# melody.net
KiCad netlist of a schematic drawn in EAGLE
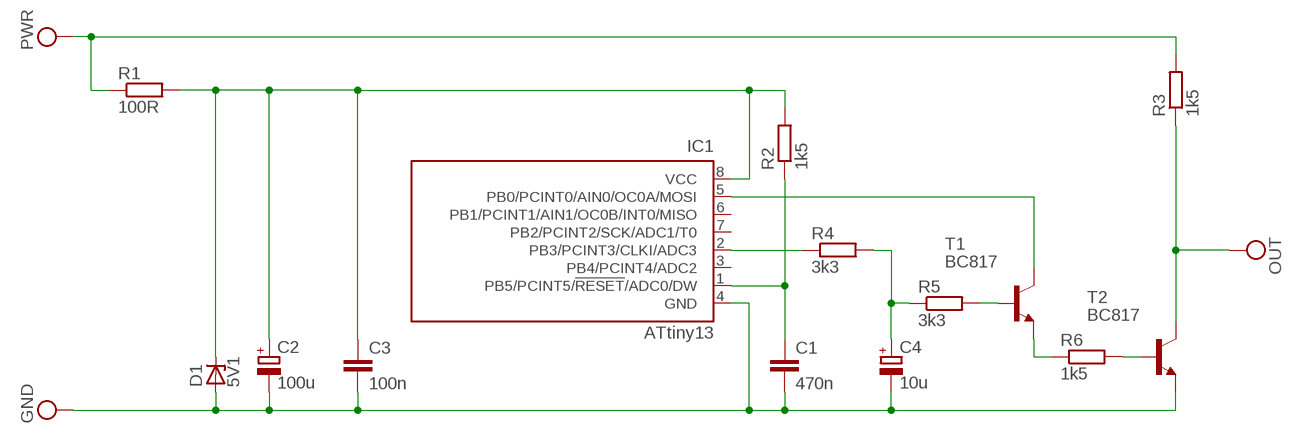
[diagram p0: schematic, sheet 1]

(export (version "E")
  (design (tool "Eeschema 10.0.6"))
  (components
    (comp (ref "C1")
      (value "470n")
      (footprint "eagle-import:C2.5-3")
      (libsource (lib "eagle-import") (part "C2,5-3"))
    )
    (comp (ref "C2")
      (value "100u")
      (footprint "eagle-import:085CS_1AR")
      (libsource (lib "eagle-import") (part "CPOL-EU085CS-1AR"))
    )
    (comp (ref "C3")
      (value "100n")
      (footprint "eagle-import:C2.5-3")
      (libsource (lib "eagle-import") (part "C2,5-3"))
    )
    (comp (ref "C4")
      (value "10u")
      (footprint "eagle-import:085CS_1AR")
      (libsource (lib "eagle-import") (part "CPOL-EU085CS-1AR"))
    )
    (comp (ref "D1")
      (value "5V1")
      (footprint "eagle-import:DO41Z10")
      (libsource (lib "eagle-import") (part "BZX85"))
    )
    (comp (ref "IC1")
      (value "ATtiny13")
      (footprint "eagle-import:DIL08")
      (fields (field (name "MPN") "ATTINY13-20PU"))
      (libsource (lib "eagle-import") (part "TINY13PU-20"))
    )
    (comp (ref "R1")
      (value "100R")
      (footprint "eagle-import:0204V")
      (libsource (lib "eagle-import") (part "R-EU_0204/2V"))
    )
    (comp (ref "R2")
      (value "1k5")
      (footprint "eagle-import:0204V")
      (libsource (lib "eagle-import") (part "R-EU_0204/2V"))
    )
    (comp (ref "R3")
      (value "1k5")
      (footprint "eagle-import:0204V")
      (libsource (lib "eagle-import") (part "R-EU_0204/2V"))
    )
    (comp (ref "R4")
      (value "3k3")
      (footprint "eagle-import:0204V")
      (libsource (lib "eagle-import") (part "R-EU_0204/2V"))
    )
    (comp (ref "R5")
      (value "3k3")
      (footprint "eagle-import:0204V")
      (libsource (lib "eagle-import") (part "R-EU_0204/2V"))
    )
    (comp (ref "R6")
      (value "1k5")
      (footprint "eagle-import:0204V")
      (libsource (lib "eagle-import") (part "R-EU_0204/2V"))
    )
    (comp (ref "T1")
      (value "BC817")
      (footprint "eagle-import:SOT23-EBC")
      (libsource (lib "eagle-import") (part "-NPN-SOT23-EBC"))
    )
    (comp (ref "T2")
      (value "BC817")
      (footprint "eagle-import:SOT23-EBC")
      (libsource (lib "eagle-import") (part "-NPN-SOT23-EBC"))
    )
  )
  (nets
    (net (code "1") (name "GND") (class "Default")
      (node (ref "C1") (pin "2") (pinfunction "2_2") (pintype "passive"))
      (node (ref "C2") (pin "-") (pinfunction "-_-") (pintype "passive"))
      (node (ref "C3") (pin "2") (pinfunction "2_2") (pintype "passive"))
      (node (ref "C4") (pin "-") (pinfunction "-_-") (pintype "passive"))
      (node (ref "D1") (pin "A") (pinfunction "A_A") (pintype "passive"))
      (node (ref "IC1") (pin "4") (pinfunction "GND_4") (pintype "power_in"))
      (node (ref "R1") (pin "1") (pinfunction "1_1") (pintype "passive"))
      (node (ref "R3") (pin "1") (pinfunction "1_1") (pintype "passive"))
      (node (ref "R3") (pin "2") (pinfunction "2_2") (pintype "passive"))
      (node (ref "T2") (pin "C") (pinfunction "C_C") (pintype "passive"))
      (node (ref "T2") (pin "E") (pinfunction "E_E") (pintype "passive"))
    )
    (net (code "2") (name "Net-(C4-Pad+)") (class "Default")
      (node (ref "C4") (pin "+") (pinfunction "+_+") (pintype "passive"))
      (node (ref "R4") (pin "2") (pinfunction "2_2") (pintype "passive"))
      (node (ref "R5") (pin "1") (pinfunction "1_1") (pintype "passive"))
    )
    (net (code "3") (name "Net-(IC1-PB0{slash}PCINT0{slash}AIN0{slash}OC0A{slash}MOSI)") (class "Default")
      (node (ref "IC1") (pin "5") (pinfunction "PB0/PCINT0/AIN0/OC0A/MOSI_5") (pintype "bidirectional"))
      (node (ref "T1") (pin "C") (pinfunction "C_C") (pintype "passive"))
    )
    (net (code "4") (name "Net-(IC1-PB3{slash}PCINT3{slash}CLKI{slash}ADC3)") (class "Default")
      (node (ref "IC1") (pin "2") (pinfunction "PB3/PCINT3/CLKI/ADC3_2") (pintype "bidirectional"))
      (node (ref "R4") (pin "1") (pinfunction "1_1") (pintype "passive"))
    )
    (net (code "5") (name "Net-(IC1-PB5{slash}PCINT5{slash}~{RESET}{slash}ADC0{slash}DW)") (class "Default")
      (node (ref "C1") (pin "1") (pinfunction "1_1") (pintype "passive"))
      (node (ref "IC1") (pin "1") (pinfunction "PB5/PCINT5/~{RESET}/ADC0/DW_1") (pintype "bidirectional"))
      (node (ref "R2") (pin "1") (pinfunction "1_1") (pintype "passive"))
    )
    (net (code "6") (name "Net-(IC1-VCC)") (class "Default")
      (node (ref "C2") (pin "+") (pinfunction "+_+") (pintype "passive"))
      (node (ref "C3") (pin "1") (pinfunction "1_1") (pintype "passive"))
      (node (ref "D1") (pin "C") (pinfunction "C_C") (pintype "passive"))
      (node (ref "IC1") (pin "8") (pinfunction "VCC_8") (pintype "power_in"))
      (node (ref "R1") (pin "2") (pinfunction "2_2") (pintype "passive"))
      (node (ref "R2") (pin "2") (pinfunction "2_2") (pintype "passive"))
    )
    (net (code "7") (name "Net-(R5-Pad2)") (class "Default")
      (node (ref "R5") (pin "2") (pinfunction "2_2") (pintype "passive"))
      (node (ref "T1") (pin "B") (pinfunction "B_B") (pintype "passive"))
    )
    (net (code "8") (name "Net-(R6-Pad1)") (class "Default")
      (node (ref "R6") (pin "1") (pinfunction "1_1") (pintype "passive"))
      (node (ref "T1") (pin "E") (pinfunction "E_E") (pintype "passive"))
    )
    (net (code "9") (name "Net-(R6-Pad2)") (class "Default")
      (node (ref "R6") (pin "2") (pinfunction "2_2") (pintype "passive"))
      (node (ref "T2") (pin "B") (pinfunction "B_B") (pintype "passive"))
    )
    (net (code "10") (name "unconnected-(IC1-PB1{slash}PCINT1{slash}AIN1{slash}OC0B{slash}INT0{slash}MISO-Pad6)") (class "Default")
      (node (ref "IC1") (pin "6") (pinfunction "PB1/PCINT1/AIN1/OC0B/INT0/MISO_6") (pintype "bidirectional"))
    )
    (net (code "11") (name "unconnected-(IC1-PB2{slash}PCINT2{slash}SCK{slash}ADC1{slash}T0-Pad7)") (class "Default")
      (node (ref "IC1") (pin "7") (pinfunction "PB2/PCINT2/SCK/ADC1/T0_7") (pintype "bidirectional"))
    )
    (net (code "12") (name "unconnected-(IC1-PB4{slash}PCINT4{slash}ADC2-Pad3)") (class "Default")
      (node (ref "IC1") (pin "3") (pinfunction "PB4/PCINT4/ADC2_3") (pintype "bidirectional"))
    )
  )
)
